# MAGI_sUSBMeterV2.net
KiCad netlist of a schematic drawn in Altium Designer
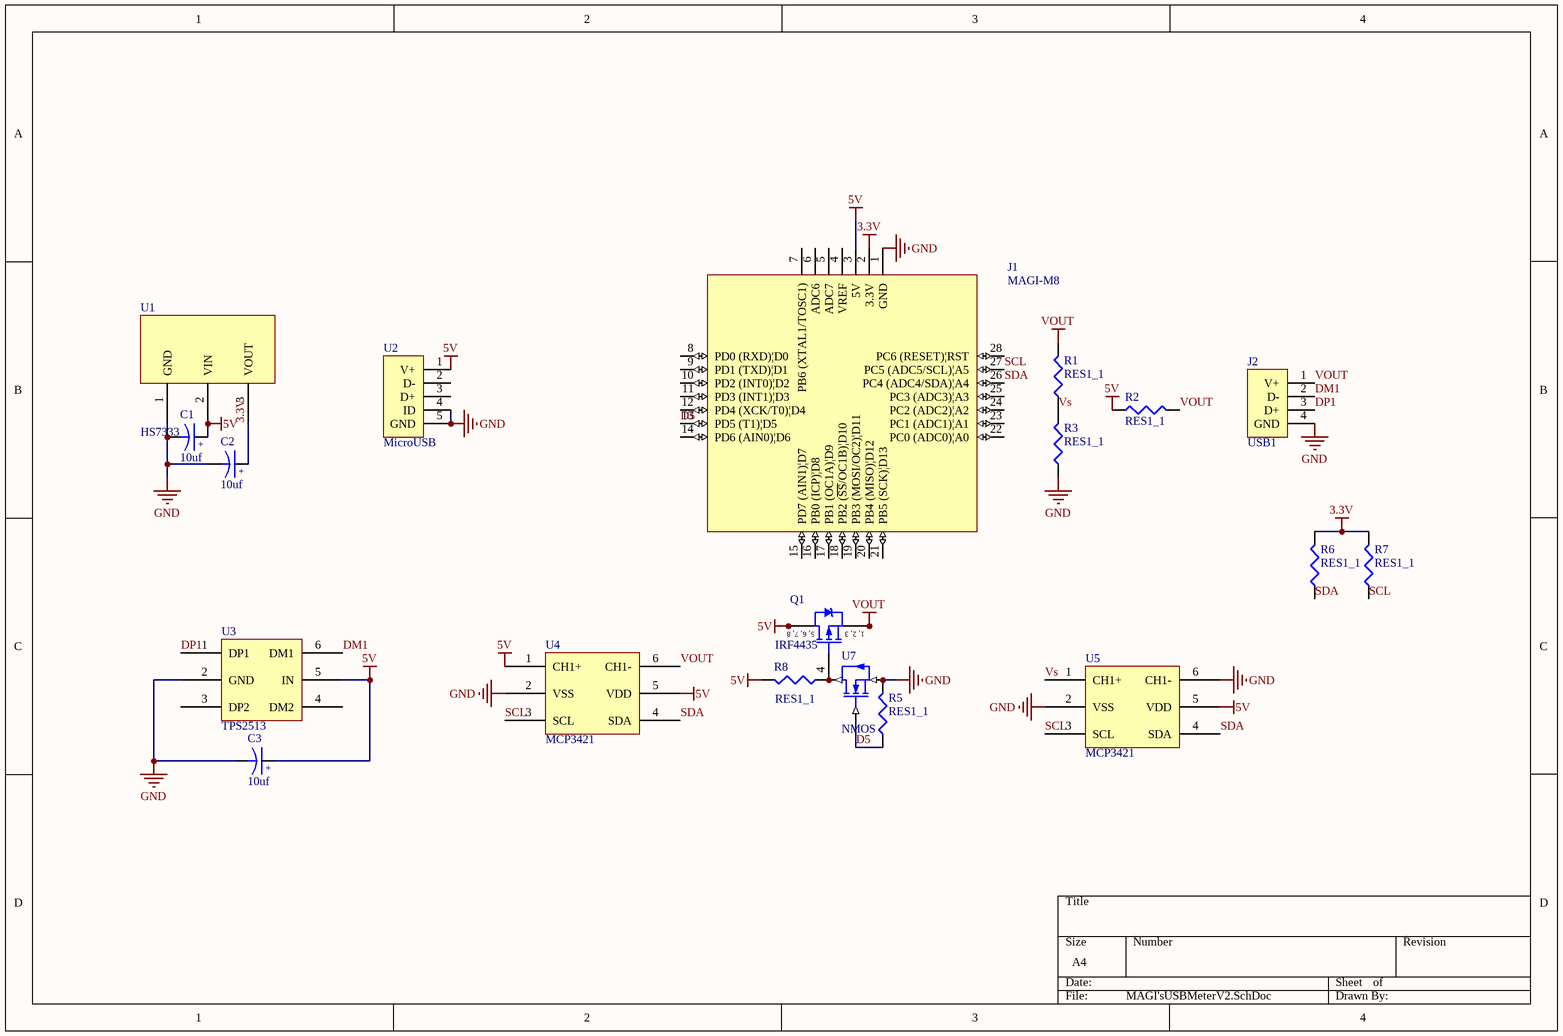
[diagram p0: MAGI'sUSBMeterV2.SchDoc]

(export (version "E")
  (design (tool "Eeschema 10.0.6"))
  (components
    (comp (ref "C1")
      (value "10uf")
      (footprint "6-0805_N")
      (description "Capacitor")
      (libsource (lib "电容器") (part "CAPACITOR POL"))
    )
    (comp (ref "C2")
      (value "10uf")
      (footprint "6-0805_N")
      (description "Capacitor")
      (libsource (lib "电容器") (part "CAPACITOR POL"))
    )
    (comp (ref "C3")
      (value "10uf")
      (footprint "6-0805_N")
      (description "Capacitor")
      (libsource (lib "电容器") (part "CAPACITOR POL"))
    )
    (comp (ref "J1") (value "MAGI-M8") (footprint "MAGI-M8") (libsource (lib "MAGI-M8") (part "MAGI-M8")))
    (comp (ref "J2") (value "USB1") (footprint "USB-04A") (libsource (lib "USB接口") (part "USB1")))
    (comp (ref "Q1")
      (value "IRF4435")
      (footprint "SO-8_N")
      (description "HEXFET Power MOSFET")
      (fields (field (name "PUBLISHER") "Altium Limited"))
      (libsource (lib "IR Discrete MOSFET - Power") (part "IRF4435"))
    )
    (comp (ref "R1") (value "RES1_1") (footprint "6-0805_N") (libsource (lib "电阻器") (part "RES1_1")))
    (comp (ref "R2") (value "RES1_1") (footprint "2512") (libsource (lib "电阻器") (part "RES1_1")))
    (comp (ref "R3") (value "RES1_1") (footprint "6-0805_N") (libsource (lib "电阻器") (part "RES1_1")))
    (comp (ref "R5") (value "RES1_1") (footprint "6-0805_N") (libsource (lib "电阻器") (part "RES1_1")))
    (comp (ref "R6") (value "RES1_1") (footprint "6-0805_N") (libsource (lib "电阻器") (part "RES1_1")))
    (comp (ref "R7") (value "RES1_1") (footprint "6-0805_N") (libsource (lib "电阻器") (part "RES1_1")))
    (comp (ref "R8") (value "RES1_1") (footprint "6-0805_N") (libsource (lib "电阻器") (part "RES1_1")))
    (comp (ref "U1") (value "HS7333") (footprint "HS7333") (libsource (lib "PMIC") (part "HS7333")))
    (comp (ref "U2") (value "MicroUSB") (footprint "microusb") (libsource (lib "USB") (part "MicroUSB2.0")))
    (comp (ref "U3") (value "TPS2513") (footprint "TPS2513") (libsource (lib "PMIC") (part "TPS2513")))
    (comp (ref "U4") (value "MCP3421") (footprint "tps2513") (libsource (lib "ADC") (part "MCP3421")))
    (comp (ref "U5") (value "MCP3421") (footprint "tps2513") (libsource (lib "ADC") (part "MCP3421")))
    (comp (ref "U7")
      (value "NMOS")
      (footprint "SOT23_n")
      (description "TO252")
      (libsource (lib "MOSFET") (part "NMOS"))
    )
  )
  (nets
    (net (code "1") (name "/D5") (class "Default")
      (node (ref "J1") (pin "13") (pinfunction "PD5_(T1)¦D5_13") (pintype "bidirectional"))
      (node (ref "R5") (pin "2") (pinfunction "2_2") (pintype "passive"))
      (node (ref "U7") (pin "3") (pinfunction "G_3") (pintype "input"))
    )
    (net (code "2") (name "/DM1") (class "Default")
      (node (ref "J2") (pin "2") (pinfunction "D-_2") (pintype "passive"))
      (node (ref "U3") (pin "6") (pinfunction "DM1_6") (pintype "passive"))
    )
    (net (code "3") (name "/DP1") (class "Default")
      (node (ref "J2") (pin "3") (pinfunction "D+_3") (pintype "passive"))
      (node (ref "U3") (pin "1") (pinfunction "DP1_1") (pintype "passive"))
    )
    (net (code "4") (name "/SCL") (class "Default")
      (node (ref "J1") (pin "27") (pinfunction "PC5_(ADC5/SCL)¦A5_27") (pintype "bidirectional"))
      (node (ref "R7") (pin "2") (pinfunction "2_2") (pintype "passive"))
      (node (ref "U4") (pin "3") (pinfunction "SCL_3") (pintype "passive"))
      (node (ref "U5") (pin "3") (pinfunction "SCL_3") (pintype "passive"))
    )
    (net (code "5") (name "/SDA") (class "Default")
      (node (ref "J1") (pin "26") (pinfunction "PC4_(ADC4/SDA)¦A4_26") (pintype "bidirectional"))
      (node (ref "R6") (pin "2") (pinfunction "2_2") (pintype "passive"))
      (node (ref "U4") (pin "4") (pinfunction "SDA_4") (pintype "passive"))
      (node (ref "U5") (pin "4") (pinfunction "SDA_4") (pintype "passive"))
    )
    (net (code "6") (name "/Vs") (class "Default")
      (node (ref "R1") (pin "1") (pinfunction "1_1") (pintype "passive"))
      (node (ref "R3") (pin "2") (pinfunction "2_2") (pintype "passive"))
      (node (ref "U5") (pin "1") (pinfunction "CH1+_1") (pintype "passive"))
    )
    (net (code "7") (name "3.3V") (class "Default")
      (node (ref "C2") (pin "1") (pinfunction "1_1") (pintype "passive"))
      (node (ref "J1") (pin "2") (pinfunction "3.3V_2") (pintype "power_in"))
      (node (ref "R6") (pin "1") (pinfunction "1_1") (pintype "passive"))
      (node (ref "R7") (pin "1") (pinfunction "1_1") (pintype "passive"))
      (node (ref "U1") (pin "3") (pinfunction "VOUT_3") (pintype "passive"))
    )
    (net (code "8") (name "5V") (class "Default")
      (node (ref "C1") (pin "1") (pinfunction "1_1") (pintype "passive"))
      (node (ref "C3") (pin "1") (pinfunction "1_1") (pintype "passive"))
      (node (ref "J1") (pin "3") (pinfunction "5V_3") (pintype "power_in"))
      (node (ref "Q1") (pin "5") (pinfunction "D_5") (pintype "passive"))
      (node (ref "Q1") (pin "6") (pinfunction "D_6") (pintype "passive"))
      (node (ref "Q1") (pin "7") (pinfunction "D_7") (pintype "passive"))
      (node (ref "Q1") (pin "8") (pinfunction "D_8") (pintype "passive"))
      (node (ref "R2") (pin "1") (pinfunction "1_1") (pintype "passive"))
      (node (ref "R8") (pin "1") (pinfunction "1_1") (pintype "passive"))
      (node (ref "U1") (pin "2") (pinfunction "VIN_2") (pintype "passive"))
      (node (ref "U2") (pin "1") (pinfunction "V+_1") (pintype "passive"))
      (node (ref "U3") (pin "5") (pinfunction "IN_5") (pintype "passive"))
      (node (ref "U4") (pin "1") (pinfunction "CH1+_1") (pintype "passive"))
      (node (ref "U4") (pin "5") (pinfunction "VDD_5") (pintype "passive"))
      (node (ref "U5") (pin "5") (pinfunction "VDD_5") (pintype "passive"))
    )
    (net (code "9") (name "GND") (class "Default")
      (node (ref "C1") (pin "2") (pinfunction "2_2") (pintype "passive"))
      (node (ref "C2") (pin "2") (pinfunction "2_2") (pintype "passive"))
      (node (ref "C3") (pin "2") (pinfunction "2_2") (pintype "passive"))
      (node (ref "J1") (pin "1") (pinfunction "GND_1") (pintype "power_in"))
      (node (ref "J2") (pin "4") (pinfunction "GND_4") (pintype "passive"))
      (node (ref "R3") (pin "1") (pinfunction "1_1") (pintype "passive"))
      (node (ref "R5") (pin "1") (pinfunction "1_1") (pintype "passive"))
      (node (ref "U1") (pin "1") (pinfunction "GND_1") (pintype "passive"))
      (node (ref "U2") (pin "4") (pinfunction "ID_4") (pintype "passive"))
      (node (ref "U2") (pin "5") (pinfunction "GND_5") (pintype "passive"))
      (node (ref "U3") (pin "2") (pinfunction "GND_2") (pintype "passive"))
      (node (ref "U4") (pin "2") (pinfunction "VSS_2") (pintype "passive"))
      (node (ref "U5") (pin "2") (pinfunction "VSS_2") (pintype "passive"))
      (node (ref "U5") (pin "6") (pinfunction "CH1-_6") (pintype "passive"))
      (node (ref "U7") (pin "2") (pinfunction "S_2") (pintype "input"))
    )
    (net (code "10") (name "Net-(Q1-G)") (class "Default")
      (node (ref "Q1") (pin "4") (pinfunction "G_4") (pintype "passive"))
      (node (ref "R8") (pin "2") (pinfunction "2_2") (pintype "passive"))
      (node (ref "U7") (pin "1") (pinfunction "D_1") (pintype "output"))
    )
    (net (code "11") (name "VOUT") (class "Default")
      (node (ref "J2") (pin "1") (pinfunction "V+_1") (pintype "passive"))
      (node (ref "Q1") (pin "1") (pinfunction "S_1") (pintype "passive"))
      (node (ref "Q1") (pin "2") (pinfunction "S_2") (pintype "passive"))
      (node (ref "Q1") (pin "3") (pinfunction "S_3") (pintype "passive"))
      (node (ref "R1") (pin "2") (pinfunction "2_2") (pintype "passive"))
      (node (ref "R2") (pin "2") (pinfunction "2_2") (pintype "passive"))
      (node (ref "U4") (pin "6") (pinfunction "CH1-_6") (pintype "passive"))
    )
    (net (code "12") (name "unconnected-(J1-ADC6-Pad6)") (class "Default")
      (node (ref "J1") (pin "6") (pinfunction "ADC6_6") (pintype "passive"))
    )
    (net (code "13") (name "unconnected-(J1-ADC7-Pad5)") (class "Default")
      (node (ref "J1") (pin "5") (pinfunction "ADC7_5") (pintype "passive"))
    )
    (net (code "14") (name "unconnected-(J1-PB0_(ICP)¦D8-Pad16)") (class "Default")
      (node (ref "J1") (pin "16") (pinfunction "PB0_(ICP)¦D8_16") (pintype "bidirectional"))
    )
    (net (code "15") (name "unconnected-(J1-PB1_(OC1A)¦D9-Pad17)") (class "Default")
      (node (ref "J1") (pin "17") (pinfunction "PB1_(OC1A)¦D9_17") (pintype "bidirectional"))
    )
    (net (code "16") (name "unconnected-(J1-PB2_(~{SS}{slash}OC1B)¦D10-Pad18)") (class "Default")
      (node (ref "J1") (pin "18") (pinfunction "PB2_(~{SS}/OC1B)¦D10_18") (pintype "bidirectional"))
    )
    (net (code "17") (name "unconnected-(J1-PB3_(MOSI{slash}OC2)¦D11-Pad19)") (class "Default")
      (node (ref "J1") (pin "19") (pinfunction "PB3_(MOSI/OC2)¦D11_19") (pintype "bidirectional"))
    )
    (net (code "18") (name "unconnected-(J1-PB4_(MISO)¦D12-Pad20)") (class "Default")
      (node (ref "J1") (pin "20") (pinfunction "PB4_(MISO)¦D12_20") (pintype "bidirectional"))
    )
    (net (code "19") (name "unconnected-(J1-PB5_(SCK)¦D13-Pad21)") (class "Default")
      (node (ref "J1") (pin "21") (pinfunction "PB5_(SCK)¦D13_21") (pintype "bidirectional"))
    )
    (net (code "20") (name "unconnected-(J1-PB6_(XTAL1{slash}TOSC1)-Pad7)") (class "Default")
      (node (ref "J1") (pin "7") (pinfunction "PB6_(XTAL1/TOSC1)_7") (pintype "passive"))
    )
    (net (code "21") (name "unconnected-(J1-PC0_(ADC0)¦A0-Pad22)") (class "Default")
      (node (ref "J1") (pin "22") (pinfunction "PC0_(ADC0)¦A0_22") (pintype "bidirectional"))
    )
    (net (code "22") (name "unconnected-(J1-PC1_(ADC1)¦A1-Pad23)") (class "Default")
      (node (ref "J1") (pin "23") (pinfunction "PC1_(ADC1)¦A1_23") (pintype "bidirectional"))
    )
    (net (code "23") (name "unconnected-(J1-PC2_(ADC2)¦A2-Pad24)") (class "Default")
      (node (ref "J1") (pin "24") (pinfunction "PC2_(ADC2)¦A2_24") (pintype "bidirectional"))
    )
    (net (code "24") (name "unconnected-(J1-PC3_(ADC3)¦A3-Pad25)") (class "Default")
      (node (ref "J1") (pin "25") (pinfunction "PC3_(ADC3)¦A3_25") (pintype "bidirectional"))
    )
    (net (code "25") (name "unconnected-(J1-PC6_(RESET)¦RST-Pad28)") (class "Default")
      (node (ref "J1") (pin "28") (pinfunction "PC6_(RESET)¦RST_28") (pintype "bidirectional"))
    )
    (net (code "26") (name "unconnected-(J1-PD0_(RXD)¦D0-Pad8)") (class "Default")
      (node (ref "J1") (pin "8") (pinfunction "PD0_(RXD)¦D0_8") (pintype "bidirectional"))
    )
    (net (code "27") (name "unconnected-(J1-PD1_(TXD)¦D1-Pad9)") (class "Default")
      (node (ref "J1") (pin "9") (pinfunction "PD1_(TXD)¦D1_9") (pintype "bidirectional"))
    )
    (net (code "28") (name "unconnected-(J1-PD2_(INT0)¦D2-Pad10)") (class "Default")
      (node (ref "J1") (pin "10") (pinfunction "PD2_(INT0)¦D2_10") (pintype "bidirectional"))
    )
    (net (code "29") (name "unconnected-(J1-PD3_(INT1)¦D3-Pad11)") (class "Default")
      (node (ref "J1") (pin "11") (pinfunction "PD3_(INT1)¦D3_11") (pintype "bidirectional"))
    )
    (net (code "30") (name "unconnected-(J1-PD4_(XCK{slash}T0)¦D4-Pad12)") (class "Default")
      (node (ref "J1") (pin "12") (pinfunction "PD4_(XCK/T0)¦D4_12") (pintype "bidirectional"))
    )
    (net (code "31") (name "unconnected-(J1-PD6_(AIN0)¦D6-Pad14)") (class "Default")
      (node (ref "J1") (pin "14") (pinfunction "PD6_(AIN0)¦D6_14") (pintype "bidirectional"))
    )
    (net (code "32") (name "unconnected-(J1-PD7_(AIN1)¦D7-Pad15)") (class "Default")
      (node (ref "J1") (pin "15") (pinfunction "PD7_(AIN1)¦D7_15") (pintype "bidirectional"))
    )
    (net (code "33") (name "unconnected-(J1-VREF-Pad4)") (class "Default")
      (node (ref "J1") (pin "4") (pinfunction "VREF_4") (pintype "passive"))
    )
    (net (code "34") (name "unconnected-(U2-D+-Pad3)") (class "Default")
      (node (ref "U2") (pin "3") (pinfunction "D+_3") (pintype "passive"))
    )
    (net (code "35") (name "unconnected-(U2-D--Pad2)") (class "Default")
      (node (ref "U2") (pin "2") (pinfunction "D-_2") (pintype "passive"))
    )
    (net (code "36") (name "unconnected-(U3-DM2-Pad4)") (class "Default")
      (node (ref "U3") (pin "4") (pinfunction "DM2_4") (pintype "passive"))
    )
    (net (code "37") (name "unconnected-(U3-DP2-Pad3)") (class "Default")
      (node (ref "U3") (pin "3") (pinfunction "DP2_3") (pintype "passive"))
    )
  )
)
